# bat_mini_grr.net
KiCad netlist of a schematic drawn in EAGLE
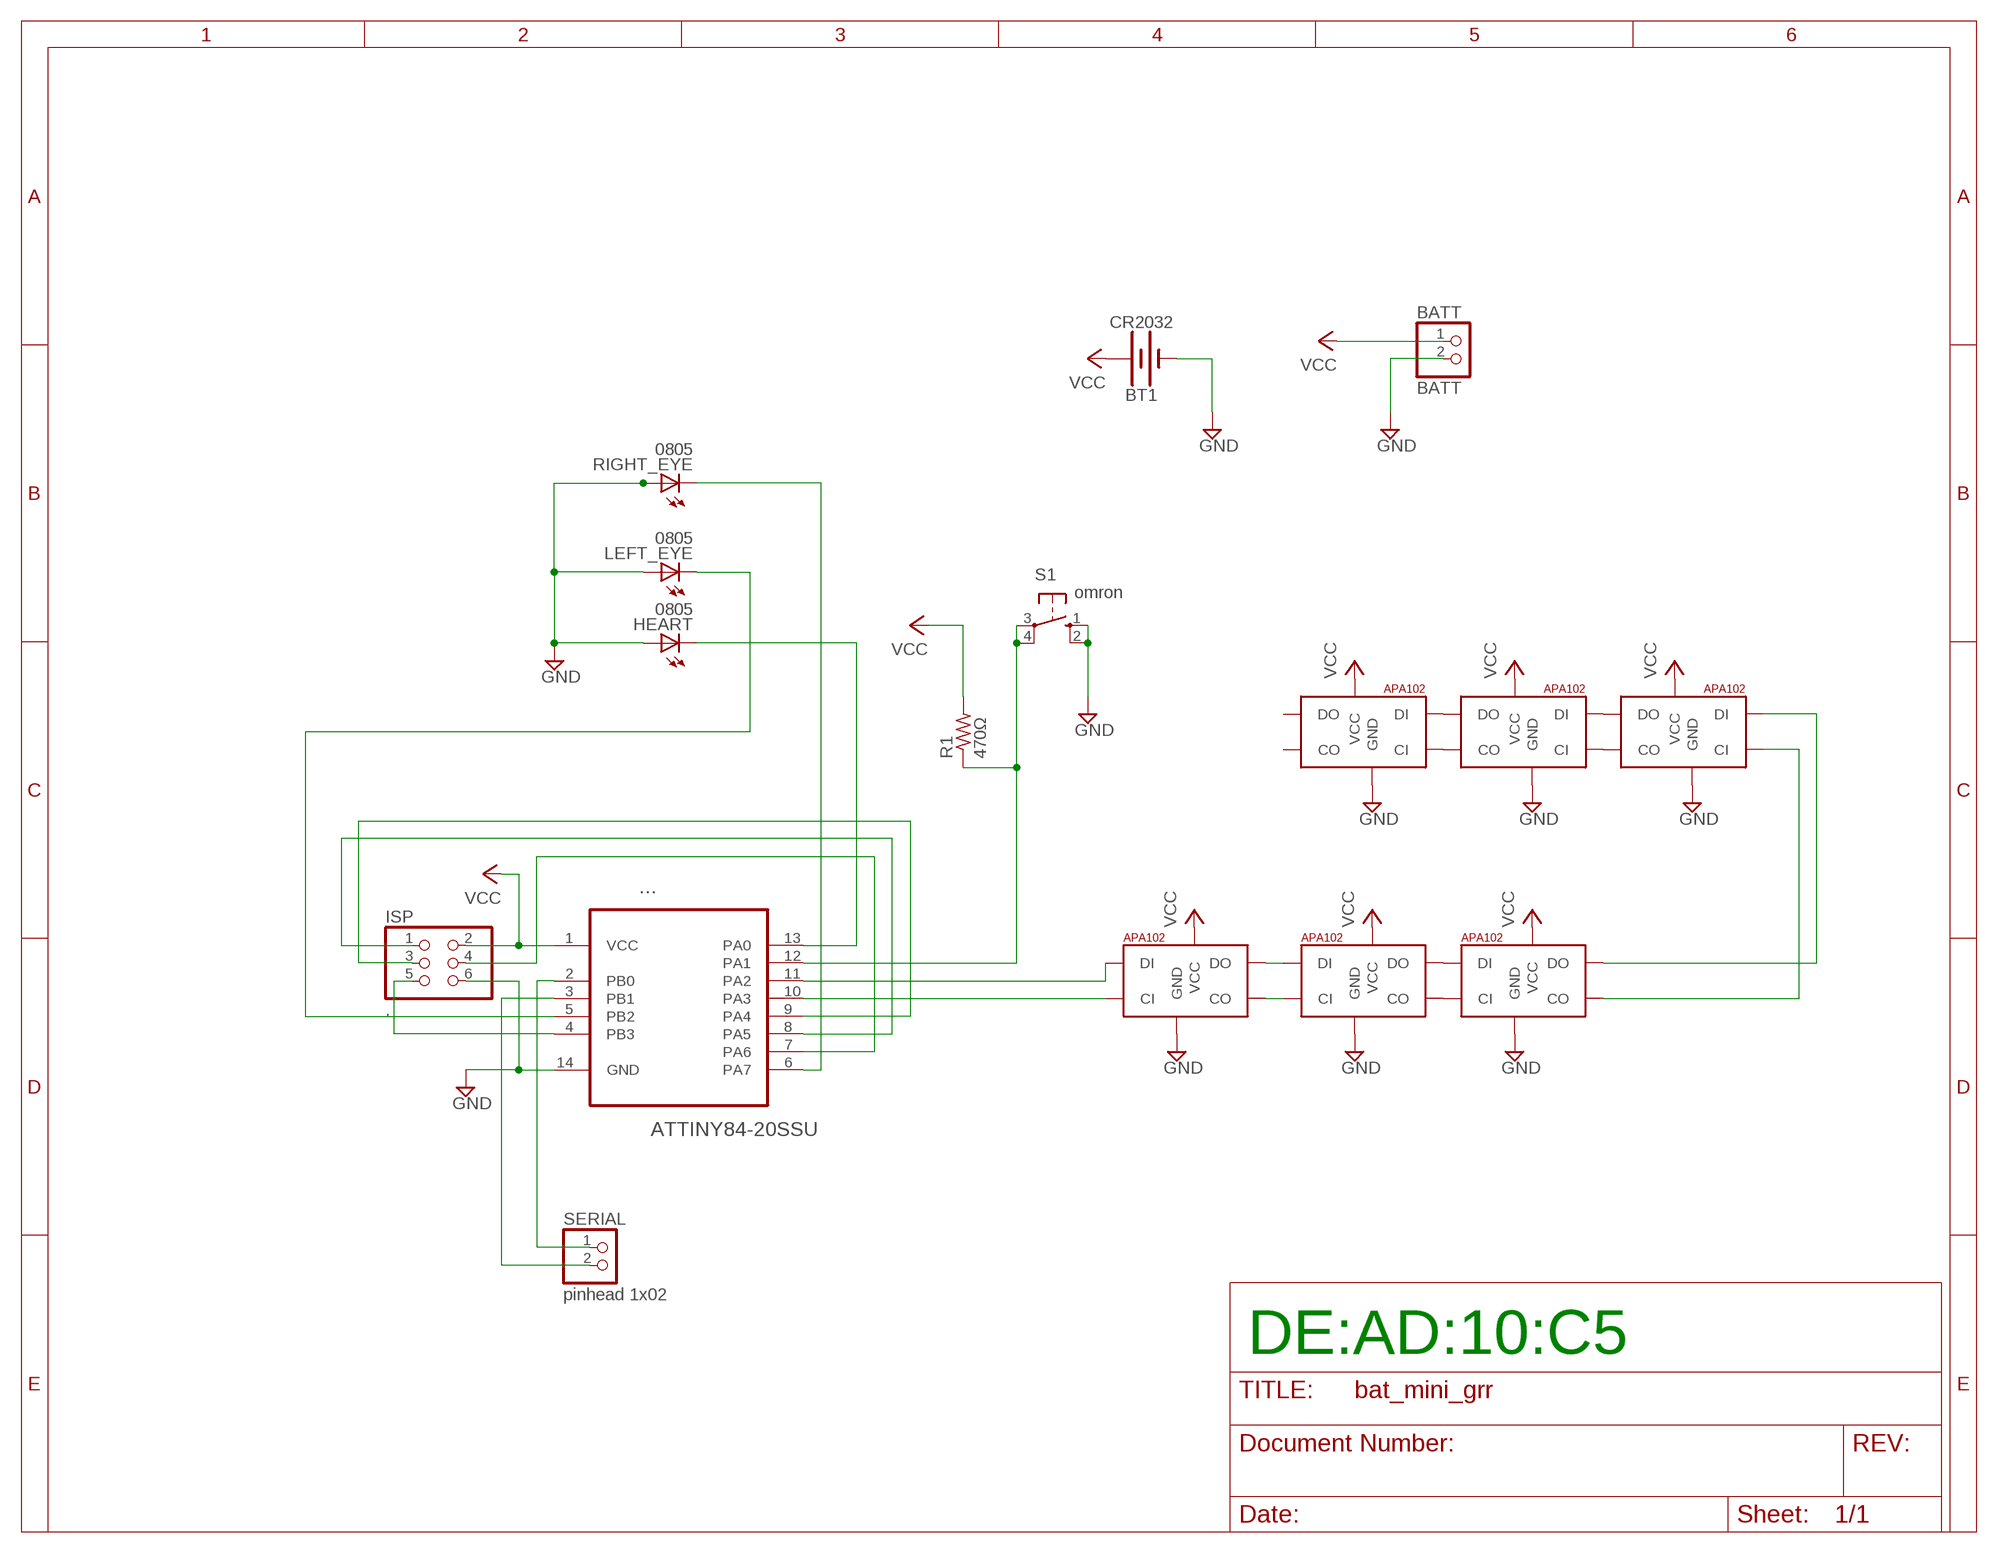
[diagram p0: schematic, sheet 1]

(export (version "E")
  (design (tool "Eeschema 10.0.6"))
  (components
    (comp (ref "...")
      (value "ATTINY84-20SSU")
      (footprint "eagle-import:SOIC127P600X175-14N")
      (libsource (lib "eagle-import") (part "ATTINY84-20SSU"))
    )
    (comp (ref "BATT")
      (value "BATT")
      (footprint "eagle-import:1X02")
      (libsource (lib "eagle-import") (part "PINHD-1X2"))
    )
    (comp (ref "BT1")
      (value "CR2032")
      (footprint "eagle-import:BATTCON_20MM_4LEGS")
      (libsource (lib "eagle-import") (part "BATTERY-20MM_SMD_4LEGS"))
    )
    (comp (ref "HEART")
      (value "0805")
      (footprint "eagle-import:CHIP-LED0805")
      (libsource (lib "eagle-import") (part "LEDCHIP-LED0805"))
    )
    (comp (ref "ISP")
      (value ".")
      (footprint "eagle-import:2X03")
      (libsource (lib "eagle-import") (part "PINHD-2X3"))
    )
    (comp (ref "LEFT_EYE")
      (value "0805")
      (footprint "eagle-import:CHIP-LED0805")
      (libsource (lib "eagle-import") (part "LEDCHIP-LED0805"))
    )
    (comp (ref "R1")
      (value "470Ω")
      (footprint "eagle-import:R0805")
      (libsource (lib "eagle-import") (part "R-US_R0805"))
    )
    (comp (ref "RIGHT_EYE")
      (value "0805")
      (footprint "eagle-import:CHIP-LED0805")
      (libsource (lib "eagle-import") (part "LEDCHIP-LED0805"))
    )
    (comp (ref "S1")
      (value "omron")
      (footprint "eagle-import:B3F-10XX")
      (fields (field (name "MPN") "B3F-1000"))
      (libsource (lib "eagle-import") (part "10-XX"))
    )
    (comp (ref "SERIAL")
      (value "pinhead 1x02")
      (footprint "eagle-import:1X02")
      (libsource (lib "eagle-import") (part "PINHD-1X2"))
    )
    (comp (ref "U$1")
      (value "APA1025050")
      (footprint "eagle-import:APA102_5050")
      (libsource (lib "eagle-import") (part "APA1025050"))
    )
    (comp (ref "U$2")
      (value "APA1025050")
      (footprint "eagle-import:APA102_5050")
      (libsource (lib "eagle-import") (part "APA1025050"))
    )
    (comp (ref "U$3")
      (value "APA1025050")
      (footprint "eagle-import:APA102_5050")
      (libsource (lib "eagle-import") (part "APA1025050"))
    )
    (comp (ref "U$5")
      (value "APA1025050")
      (footprint "eagle-import:APA102_5050")
      (libsource (lib "eagle-import") (part "APA1025050"))
    )
    (comp (ref "U$6")
      (value "APA1025050")
      (footprint "eagle-import:APA102_5050")
      (libsource (lib "eagle-import") (part "APA1025050"))
    )
    (comp (ref "U$7")
      (value "APA1025050")
      (footprint "eagle-import:APA102_5050")
      (libsource (lib "eagle-import") (part "APA1025050"))
    )
  )
  (nets
    (net (code "1") (name "GND") (class "Default")
      (node (ref "...") (pin "14") (pinfunction "GND_14") (pintype "passive"))
      (node (ref "BATT") (pin "2") (pinfunction "2_2") (pintype "passive"))
      (node (ref "BT1") (pin "NEGATIVE") (pinfunction "-_NEGATIVE") (pintype "power_in"))
      (node (ref "HEART") (pin "A") (pinfunction "A_A") (pintype "passive"))
      (node (ref "ISP") (pin "6") (pinfunction "6_6") (pintype "passive"))
      (node (ref "LEFT_EYE") (pin "A") (pinfunction "A_A") (pintype "passive"))
      (node (ref "RIGHT_EYE") (pin "A") (pinfunction "A_A") (pintype "passive"))
      (node (ref "S1") (pin "1") (pinfunction "S_1") (pintype "passive"))
      (node (ref "S1") (pin "2") (pinfunction "S1_2") (pintype "passive"))
      (node (ref "U$1") (pin "6") (pinfunction "GND_6") (pintype "bidirectional"))
      (node (ref "U$2") (pin "6") (pinfunction "GND_6") (pintype "bidirectional"))
      (node (ref "U$3") (pin "6") (pinfunction "GND_6") (pintype "bidirectional"))
      (node (ref "U$5") (pin "6") (pinfunction "GND_6") (pintype "bidirectional"))
      (node (ref "U$6") (pin "6") (pinfunction "GND_6") (pintype "bidirectional"))
      (node (ref "U$7") (pin "6") (pinfunction "GND_6") (pintype "bidirectional"))
    )
    (net (code "2") (name "Net-(...-PA0)") (class "Default")
      (node (ref "...") (pin "13") (pinfunction "PA0_13") (pintype "bidirectional"))
      (node (ref "HEART") (pin "C") (pinfunction "C_C") (pintype "passive"))
    )
    (net (code "3") (name "Net-(...-PA1)") (class "Default")
      (node (ref "...") (pin "12") (pinfunction "PA1_12") (pintype "bidirectional"))
      (node (ref "R1") (pin "1") (pinfunction "1_1") (pintype "passive"))
      (node (ref "S1") (pin "3") (pinfunction "P_3") (pintype "passive"))
      (node (ref "S1") (pin "4") (pinfunction "P1_4") (pintype "passive"))
    )
    (net (code "4") (name "Net-(...-PA2)") (class "Default")
      (node (ref "...") (pin "11") (pinfunction "PA2_11") (pintype "bidirectional"))
      (node (ref "U$1") (pin "4") (pinfunction "DI_4") (pintype "bidirectional"))
    )
    (net (code "5") (name "Net-(...-PA3)") (class "Default")
      (node (ref "...") (pin "10") (pinfunction "PA3_10") (pintype "bidirectional"))
      (node (ref "U$1") (pin "5") (pinfunction "CI_5") (pintype "bidirectional"))
    )
    (net (code "6") (name "Net-(...-PA4)") (class "Default")
      (node (ref "...") (pin "9") (pinfunction "PA4_9") (pintype "bidirectional"))
      (node (ref "ISP") (pin "3") (pinfunction "3_3") (pintype "passive"))
    )
    (net (code "7") (name "Net-(...-PA5)") (class "Default")
      (node (ref "...") (pin "8") (pinfunction "PA5_8") (pintype "bidirectional"))
      (node (ref "ISP") (pin "1") (pinfunction "1_1") (pintype "passive"))
    )
    (net (code "8") (name "Net-(...-PA6)") (class "Default")
      (node (ref "...") (pin "7") (pinfunction "PA6_7") (pintype "bidirectional"))
      (node (ref "ISP") (pin "4") (pinfunction "4_4") (pintype "passive"))
    )
    (net (code "9") (name "Net-(...-PA7)") (class "Default")
      (node (ref "...") (pin "6") (pinfunction "PA7_6") (pintype "bidirectional"))
      (node (ref "RIGHT_EYE") (pin "C") (pinfunction "C_C") (pintype "passive"))
    )
    (net (code "10") (name "Net-(...-PB0)") (class "Default")
      (node (ref "...") (pin "2") (pinfunction "PB0_2") (pintype "bidirectional"))
      (node (ref "SERIAL") (pin "1") (pinfunction "1_1") (pintype "passive"))
    )
    (net (code "11") (name "Net-(...-PB1)") (class "Default")
      (node (ref "...") (pin "3") (pinfunction "PB1_3") (pintype "bidirectional"))
      (node (ref "SERIAL") (pin "2") (pinfunction "2_2") (pintype "passive"))
    )
    (net (code "12") (name "Net-(...-PB2)") (class "Default")
      (node (ref "...") (pin "5") (pinfunction "PB2_5") (pintype "bidirectional"))
      (node (ref "LEFT_EYE") (pin "C") (pinfunction "C_C") (pintype "passive"))
    )
    (net (code "13") (name "Net-(...-PB3)") (class "Default")
      (node (ref "...") (pin "4") (pinfunction "PB3_4") (pintype "bidirectional"))
      (node (ref "ISP") (pin "5") (pinfunction "5_5") (pintype "passive"))
    )
    (net (code "14") (name "Net-(U$1-CO)") (class "Default")
      (node (ref "U$1") (pin "2") (pinfunction "CO_2") (pintype "bidirectional"))
      (node (ref "U$2") (pin "5") (pinfunction "CI_5") (pintype "bidirectional"))
    )
    (net (code "15") (name "Net-(U$1-DO)") (class "Default")
      (node (ref "U$1") (pin "3") (pinfunction "DO_3") (pintype "bidirectional"))
      (node (ref "U$2") (pin "4") (pinfunction "DI_4") (pintype "bidirectional"))
    )
    (net (code "16") (name "Net-(U$2-CO)") (class "Default")
      (node (ref "U$2") (pin "2") (pinfunction "CO_2") (pintype "bidirectional"))
      (node (ref "U$3") (pin "5") (pinfunction "CI_5") (pintype "bidirectional"))
    )
    (net (code "17") (name "Net-(U$2-DO)") (class "Default")
      (node (ref "U$2") (pin "3") (pinfunction "DO_3") (pintype "bidirectional"))
      (node (ref "U$3") (pin "4") (pinfunction "DI_4") (pintype "bidirectional"))
    )
    (net (code "18") (name "Net-(U$3-CO)") (class "Default")
      (node (ref "U$3") (pin "2") (pinfunction "CO_2") (pintype "bidirectional"))
      (node (ref "U$5") (pin "5") (pinfunction "CI_5") (pintype "bidirectional"))
    )
    (net (code "19") (name "Net-(U$3-DO)") (class "Default")
      (node (ref "U$3") (pin "3") (pinfunction "DO_3") (pintype "bidirectional"))
      (node (ref "U$5") (pin "4") (pinfunction "DI_4") (pintype "bidirectional"))
    )
    (net (code "20") (name "Net-(U$5-CO)") (class "Default")
      (node (ref "U$5") (pin "2") (pinfunction "CO_2") (pintype "bidirectional"))
      (node (ref "U$6") (pin "5") (pinfunction "CI_5") (pintype "bidirectional"))
    )
    (net (code "21") (name "Net-(U$5-DO)") (class "Default")
      (node (ref "U$5") (pin "3") (pinfunction "DO_3") (pintype "bidirectional"))
      (node (ref "U$6") (pin "4") (pinfunction "DI_4") (pintype "bidirectional"))
    )
    (net (code "22") (name "Net-(U$6-CO)") (class "Default")
      (node (ref "U$6") (pin "2") (pinfunction "CO_2") (pintype "bidirectional"))
      (node (ref "U$7") (pin "5") (pinfunction "CI_5") (pintype "bidirectional"))
    )
    (net (code "23") (name "Net-(U$6-DO)") (class "Default")
      (node (ref "U$6") (pin "3") (pinfunction "DO_3") (pintype "bidirectional"))
      (node (ref "U$7") (pin "4") (pinfunction "DI_4") (pintype "bidirectional"))
    )
    (net (code "24") (name "VCC") (class "Default")
      (node (ref "...") (pin "1") (pinfunction "VCC_1") (pintype "power_in"))
      (node (ref "BATT") (pin "1") (pinfunction "1_1") (pintype "passive"))
      (node (ref "BT1") (pin "POSITIVE@1") (pinfunction "+_POSITIVE@1") (pintype "power_in"))
      (node (ref "BT1") (pin "POSITIVE@2") (pinfunction "+_POSITIVE@2") (pintype "power_in"))
      (node (ref "BT1") (pin "POSITIVE@3") (pinfunction "+_POSITIVE@3") (pintype "power_in"))
      (node (ref "BT1") (pin "POSITIVE@4") (pinfunction "+_POSITIVE@4") (pintype "power_in"))
      (node (ref "ISP") (pin "2") (pinfunction "2_2") (pintype "passive"))
      (node (ref "R1") (pin "2") (pinfunction "2_2") (pintype "passive"))
      (node (ref "U$1") (pin "1") (pinfunction "VCC_1") (pintype "bidirectional"))
      (node (ref "U$2") (pin "1") (pinfunction "VCC_1") (pintype "bidirectional"))
      (node (ref "U$3") (pin "1") (pinfunction "VCC_1") (pintype "bidirectional"))
      (node (ref "U$5") (pin "1") (pinfunction "VCC_1") (pintype "bidirectional"))
      (node (ref "U$6") (pin "1") (pinfunction "VCC_1") (pintype "bidirectional"))
      (node (ref "U$7") (pin "1") (pinfunction "VCC_1") (pintype "bidirectional"))
    )
    (net (code "25") (name "unconnected-(U$7-CO-Pad2)") (class "Default")
      (node (ref "U$7") (pin "2") (pinfunction "CO_2") (pintype "bidirectional"))
    )
    (net (code "26") (name "unconnected-(U$7-DO-Pad3)") (class "Default")
      (node (ref "U$7") (pin "3") (pinfunction "DO_3") (pintype "bidirectional"))
    )
  )
)
